# Lab1.net
KiCad netlist of a schematic drawn in EAGLE
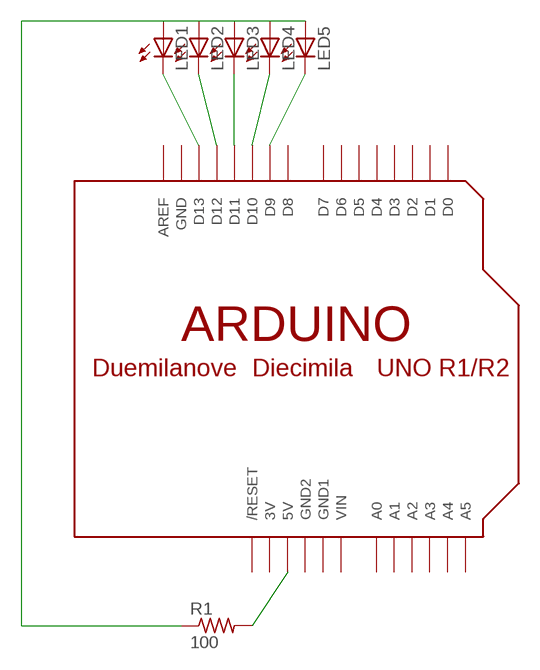
[diagram p0: schematic, sheet 1]

(export (version "E")
  (design (tool "Eeschema 10.0.6"))
  (components
    (comp (ref "LED1")
      (value "LED5MM")
      (footprint "eagle-import:LED5MM")
      (libsource (lib "eagle-import") (part "LED5MM"))
    )
    (comp (ref "LED2")
      (value "LED5MM")
      (footprint "eagle-import:LED5MM")
      (libsource (lib "eagle-import") (part "LED5MM"))
    )
    (comp (ref "LED3")
      (value "LED5MM")
      (footprint "eagle-import:LED5MM")
      (libsource (lib "eagle-import") (part "LED5MM"))
    )
    (comp (ref "LED4")
      (value "LED5MM")
      (footprint "eagle-import:LED5MM")
      (libsource (lib "eagle-import") (part "LED5MM"))
    )
    (comp (ref "LED5")
      (value "LED5MM")
      (footprint "eagle-import:LED5MM")
      (libsource (lib "eagle-import") (part "LED5MM"))
    )
    (comp (ref "R1")
      (value "100")
      (footprint "eagle-import:0411_12")
      (libsource (lib "eagle-import") (part "R-US_0411/12"))
    )
    (comp (ref "U$1")
      (value "ARDUINO-BPLACE")
      (footprint "eagle-import:ARDUINO-BPLACE")
      (libsource (lib "eagle-import") (part "ARDUINO-BPLACE"))
    )
  )
  (nets
    (net (code "1") (name "/3V") (class "Default")
      (node (ref "U$1") (pin "3V") (pinfunction "3V_3V") (pintype "power_in"))
    )
    (net (code "2") (name "/GND") (class "Default")
      (node (ref "U$1") (pin "GND") (pinfunction "GND_GND") (pintype "power_in"))
    )
    (net (code "3") (name "/GND1") (class "Default")
      (node (ref "U$1") (pin "GND1") (pinfunction "GND1_GND1") (pintype "power_in"))
    )
    (net (code "4") (name "/GND2") (class "Default")
      (node (ref "U$1") (pin "GND2") (pinfunction "GND2_GND2") (pintype "power_in"))
    )
    (net (code "5") (name "/VIN") (class "Default")
      (node (ref "U$1") (pin "VIN") (pinfunction "VIN_VIN") (pintype "power_in"))
    )
    (net (code "6") (name "Net-(LED1-C)") (class "Default")
      (node (ref "LED1") (pin "K") (pinfunction "C_K") (pintype "passive"))
      (node (ref "U$1") (pin "D13") (pinfunction "D13_D13") (pintype "bidirectional"))
    )
    (net (code "7") (name "Net-(LED2-C)") (class "Default")
      (node (ref "LED2") (pin "K") (pinfunction "C_K") (pintype "passive"))
      (node (ref "U$1") (pin "D12") (pinfunction "D12_D12") (pintype "bidirectional"))
    )
    (net (code "8") (name "Net-(LED3-C)") (class "Default")
      (node (ref "LED3") (pin "K") (pinfunction "C_K") (pintype "passive"))
      (node (ref "U$1") (pin "D11") (pinfunction "D11_D11") (pintype "bidirectional"))
    )
    (net (code "9") (name "Net-(LED4-C)") (class "Default")
      (node (ref "LED4") (pin "K") (pinfunction "C_K") (pintype "passive"))
      (node (ref "U$1") (pin "D10") (pinfunction "D10_D10") (pintype "bidirectional"))
    )
    (net (code "10") (name "Net-(LED5-C)") (class "Default")
      (node (ref "LED5") (pin "K") (pinfunction "C_K") (pintype "passive"))
      (node (ref "U$1") (pin "D9") (pinfunction "D9_D9") (pintype "bidirectional"))
    )
    (net (code "11") (name "Net-(LED5-PadA)") (class "Default")
      (node (ref "LED5") (pin "A") (pinfunction "A_A") (pintype "passive"))
      (node (ref "R1") (pin "1") (pinfunction "1_1") (pintype "passive"))
    )
    (net (code "12") (name "Net-(R1-Pad2)") (class "Default")
      (node (ref "R1") (pin "2") (pinfunction "2_2") (pintype "passive"))
      (node (ref "U$1") (pin "5V") (pinfunction "5V_5V") (pintype "power_in"))
    )
    (net (code "13") (name "unconnected-(LED1-PadA)") (class "Default")
      (node (ref "LED1") (pin "A") (pinfunction "A_A") (pintype "passive"))
    )
    (net (code "14") (name "unconnected-(LED2-PadA)") (class "Default")
      (node (ref "LED2") (pin "A") (pinfunction "A_A") (pintype "passive"))
    )
    (net (code "15") (name "unconnected-(LED3-PadA)") (class "Default")
      (node (ref "LED3") (pin "A") (pinfunction "A_A") (pintype "passive"))
    )
    (net (code "16") (name "unconnected-(LED4-PadA)") (class "Default")
      (node (ref "LED4") (pin "A") (pinfunction "A_A") (pintype "passive"))
    )
    (net (code "17") (name "unconnected-(U$1-PadA0)") (class "Default")
      (node (ref "U$1") (pin "A0") (pinfunction "A0_A0") (pintype "bidirectional"))
    )
    (net (code "18") (name "unconnected-(U$1-PadA1)") (class "Default")
      (node (ref "U$1") (pin "A1") (pinfunction "A1_A1") (pintype "bidirectional"))
    )
    (net (code "19") (name "unconnected-(U$1-PadA2)") (class "Default")
      (node (ref "U$1") (pin "A2") (pinfunction "A2_A2") (pintype "bidirectional"))
    )
    (net (code "20") (name "unconnected-(U$1-PadA3)") (class "Default")
      (node (ref "U$1") (pin "A3") (pinfunction "A3_A3") (pintype "bidirectional"))
    )
    (net (code "21") (name "unconnected-(U$1-PadA4)") (class "Default")
      (node (ref "U$1") (pin "A4") (pinfunction "A4_A4") (pintype "bidirectional"))
    )
    (net (code "22") (name "unconnected-(U$1-PadA5)") (class "Default")
      (node (ref "U$1") (pin "A5") (pinfunction "A5_A5") (pintype "bidirectional"))
    )
    (net (code "23") (name "unconnected-(U$1-PadAREF)") (class "Default")
      (node (ref "U$1") (pin "AREF") (pinfunction "AREF_AREF") (pintype "bidirectional"))
    )
    (net (code "24") (name "unconnected-(U$1-PadD0)") (class "Default")
      (node (ref "U$1") (pin "D0") (pinfunction "D0_D0") (pintype "bidirectional"))
    )
    (net (code "25") (name "unconnected-(U$1-PadD1)") (class "Default")
      (node (ref "U$1") (pin "D1") (pinfunction "D1_D1") (pintype "bidirectional"))
    )
    (net (code "26") (name "unconnected-(U$1-PadD2)") (class "Default")
      (node (ref "U$1") (pin "D2") (pinfunction "D2_D2") (pintype "bidirectional"))
    )
    (net (code "27") (name "unconnected-(U$1-PadD3)") (class "Default")
      (node (ref "U$1") (pin "D3") (pinfunction "D3_D3") (pintype "bidirectional"))
    )
    (net (code "28") (name "unconnected-(U$1-PadD4)") (class "Default")
      (node (ref "U$1") (pin "D4") (pinfunction "D4_D4") (pintype "bidirectional"))
    )
    (net (code "29") (name "unconnected-(U$1-PadD5)") (class "Default")
      (node (ref "U$1") (pin "D5") (pinfunction "D5_D5") (pintype "bidirectional"))
    )
    (net (code "30") (name "unconnected-(U$1-PadD6)") (class "Default")
      (node (ref "U$1") (pin "D6") (pinfunction "D6_D6") (pintype "bidirectional"))
    )
    (net (code "31") (name "unconnected-(U$1-PadD7)") (class "Default")
      (node (ref "U$1") (pin "D7") (pinfunction "D7_D7") (pintype "bidirectional"))
    )
    (net (code "32") (name "unconnected-(U$1-PadD8)") (class "Default")
      (node (ref "U$1") (pin "D8") (pinfunction "D8_D8") (pintype "bidirectional"))
    )
    (net (code "33") (name "unconnected-(U$1-{slash}RESET-PadRESET)") (class "Default")
      (node (ref "U$1") (pin "RESET") (pinfunction "/RESET_RESET") (pintype "bidirectional"))
    )
  )
)
